# MainBoard.net
KiCad netlist of a schematic drawn in EAGLE
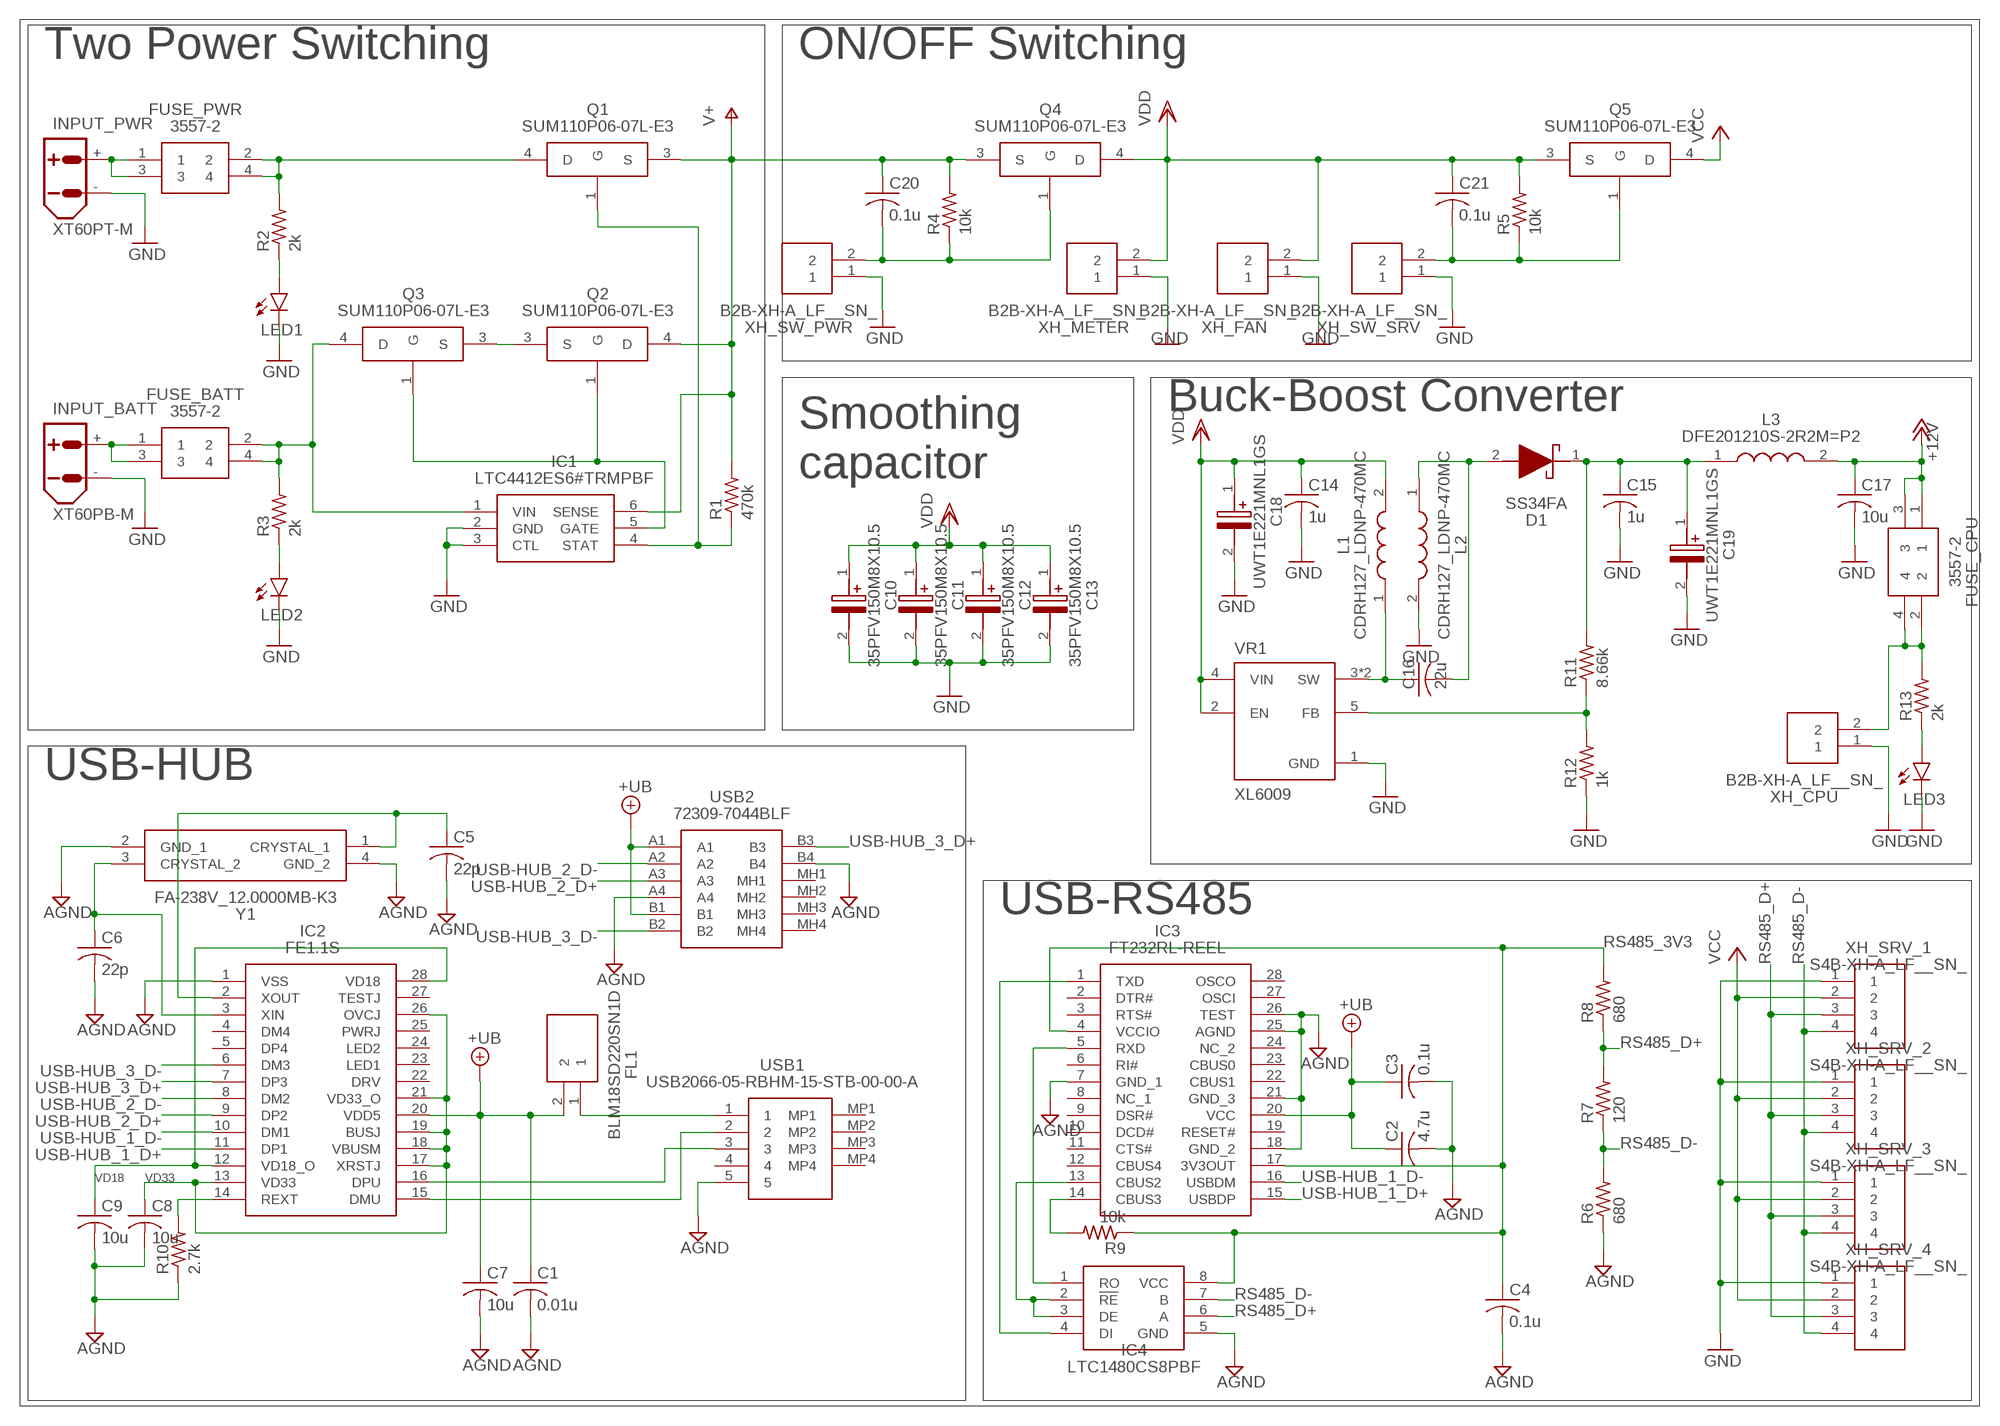
[diagram p0: schematic, sheet 1]

(export (version "E")
  (design (tool "Eeschema 10.0.6"))
  (components
    (comp (ref "C1")
      (value "0.01u")
      (footprint "eagle-import:C1608")
      (libsource (lib "eagle-import") (part "C-USC1608"))
    )
    (comp (ref "C2")
      (value "4.7u")
      (footprint "eagle-import:C1608")
      (libsource (lib "eagle-import") (part "C-USC1608"))
    )
    (comp (ref "C3")
      (value "0.1u")
      (footprint "eagle-import:C1608")
      (libsource (lib "eagle-import") (part "C-USC1608"))
    )
    (comp (ref "C4")
      (value "0.1u")
      (footprint "eagle-import:C1608")
      (libsource (lib "eagle-import") (part "C-USC1608"))
    )
    (comp (ref "C5")
      (value "22p")
      (footprint "eagle-import:C1608")
      (libsource (lib "eagle-import") (part "C-USC1608"))
    )
    (comp (ref "C6")
      (value "22p")
      (footprint "eagle-import:C1608")
      (libsource (lib "eagle-import") (part "C-USC1608"))
    )
    (comp (ref "C7")
      (value "10u")
      (footprint "eagle-import:C1608")
      (libsource (lib "eagle-import") (part "C-USC1608"))
    )
    (comp (ref "C8")
      (value "10u")
      (footprint "eagle-import:C1608")
      (libsource (lib "eagle-import") (part "C-USC1608"))
    )
    (comp (ref "C9")
      (value "10u")
      (footprint "eagle-import:C1608")
      (libsource (lib "eagle-import") (part "C-USC1608"))
    )
    (comp (ref "C10")
      (value "35PFV150M8X10.5")
      (footprint "eagle-import:CAPAE830X1050N")
      (fields (field (name "MOUSER_PART_NUMBER") "232-35PFV150M8X10.5"))
      (libsource (lib "eagle-import") (part "35PFV150M8X10.5"))
    )
    (comp (ref "C11")
      (value "35PFV150M8X10.5")
      (footprint "eagle-import:CAPAE830X1050N")
      (fields (field (name "MOUSER_PART_NUMBER") "232-35PFV150M8X10.5"))
      (libsource (lib "eagle-import") (part "35PFV150M8X10.5"))
    )
    (comp (ref "C12")
      (value "35PFV150M8X10.5")
      (footprint "eagle-import:CAPAE830X1050N")
      (fields (field (name "MOUSER_PART_NUMBER") "232-35PFV150M8X10.5"))
      (libsource (lib "eagle-import") (part "35PFV150M8X10.5"))
    )
    (comp (ref "C13")
      (value "35PFV150M8X10.5")
      (footprint "eagle-import:CAPAE830X1050N")
      (fields (field (name "MOUSER_PART_NUMBER") "232-35PFV150M8X10.5"))
      (libsource (lib "eagle-import") (part "35PFV150M8X10.5"))
    )
    (comp (ref "C14")
      (value "1u")
      (footprint "eagle-import:C1608")
      (libsource (lib "eagle-import") (part "C-USC1608"))
    )
    (comp (ref "C15")
      (value "1u")
      (footprint "eagle-import:C1608")
      (libsource (lib "eagle-import") (part "C-USC1608"))
    )
    (comp (ref "C16")
      (value "22u")
      (footprint "eagle-import:C2012")
      (libsource (lib "eagle-import") (part "C-USC2012"))
    )
    (comp (ref "C17")
      (value "10u")
      (footprint "eagle-import:C1608")
      (libsource (lib "eagle-import") (part "C-USC1608"))
    )
    (comp (ref "C18")
      (value "UWT1E221MNL1GS")
      (footprint "eagle-import:CAPAE830X1080N")
      (fields (field (name "MOUSER_PART_NUMBER") "647-UWT1E221MNL1GS"))
      (libsource (lib "eagle-import") (part "UWT1E221MNL1GS"))
    )
    (comp (ref "C19")
      (value "UWT1E221MNL1GS")
      (footprint "eagle-import:CAPAE830X1080N")
      (fields (field (name "MOUSER_PART_NUMBER") "647-UWT1E221MNL1GS"))
      (libsource (lib "eagle-import") (part "UWT1E221MNL1GS"))
    )
    (comp (ref "C20")
      (value "0.1u")
      (footprint "eagle-import:C1608")
      (libsource (lib "eagle-import") (part "C-USC1608"))
    )
    (comp (ref "C21")
      (value "0.1u")
      (footprint "eagle-import:C1608")
      (libsource (lib "eagle-import") (part "C-USC1608"))
    )
    (comp (ref "D1")
      (value "SS34FA")
      (footprint "eagle-import:SODFL3618X143N")
      (fields (field (name "MOUSER_PART_NUMBER") "512-SS34FA"))
      (libsource (lib "eagle-import") (part "SS34FA"))
    )
    (comp (ref "FL1")
      (value "BLM18SD220SN1D")
      (footprint "eagle-import:BLM18AG102BH1D")
      (fields (field (name "MOUSER_PART_NUMBER") "81-BLM18SD220SN1D"))
      (libsource (lib "eagle-import") (part "BLM18SD220SN1D"))
    )
    (comp (ref "FUSE_BATT")
      (value "3557-2")
      (footprint "eagle-import:3557-2")
      (fields (field (name "MOUSER_PART_NUMBER") "534-3557-2"))
      (libsource (lib "eagle-import") (part "3557-2"))
    )
    (comp (ref "FUSE_CPU")
      (value "3557-2")
      (footprint "eagle-import:3557-2")
      (fields (field (name "MOUSER_PART_NUMBER") "534-3557-2"))
      (libsource (lib "eagle-import") (part "3557-2"))
    )
    (comp (ref "FUSE_PWR")
      (value "3557-2")
      (footprint "eagle-import:3557-2")
      (fields (field (name "MOUSER_PART_NUMBER") "534-3557-2"))
      (libsource (lib "eagle-import") (part "3557-2"))
    )
    (comp (ref "IC1")
      (value "LTC4412ES6#TRMPBF")
      (footprint "eagle-import:SOT95P280X100-6N")
      (fields (field (name "MOUSER_PART_NUMBER") "584-LTC4412ES6TRMPBF"))
      (libsource (lib "eagle-import") (part "LTC4412ES6#TRMPBF"))
    )
    (comp (ref "IC2")
      (value "FE1.1S")
      (footprint "eagle-import:SOP64P600X175-28N")
      (libsource (lib "eagle-import") (part "FE1.1S"))
    )
    (comp (ref "IC3")
      (value "FT232RL-REEL")
      (footprint "eagle-import:SOP65P778X200-28N")
      (fields (field (name "MOUSER_PART_NUMBER") "895-FT232RL"))
      (libsource (lib "eagle-import") (part "FT232RL-REEL"))
    )
    (comp (ref "IC4")
      (value "LTC1480CS8PBF")
      (footprint "eagle-import:SOIC127P599X175-8N")
      (libsource (lib "eagle-import") (part "LTC1480CS8PBF"))
    )
    (comp (ref "INPUT_BATT")
      (value "XT60PB-M")
      (footprint "eagle-import:XT60PB-M")
      (libsource (lib "eagle-import") (part "XT60PB-M"))
    )
    (comp (ref "INPUT_PWR")
      (value "XT60PT-M")
      (footprint "eagle-import:XT60PT-M")
      (libsource (lib "eagle-import") (part "XT60PT-M"))
    )
    (comp (ref "L1")
      (value "CDRH127_LDNP-470MC")
      (footprint "eagle-import:INDPM120120X800N")
      (fields
        (field (name "MANUFACTURER_PART_NUMBER") "CDRH127/LDNP-470MC")
        (field (name "MOUSER_PART_NUMBER") "851-CDRH127LDNP470MC")
      )
      (libsource (lib "eagle-import") (part "CDRH127_LDNP-470MC"))
    )
    (comp (ref "L2")
      (value "CDRH127_LDNP-470MC")
      (footprint "eagle-import:INDPM120120X800N")
      (fields
        (field (name "MANUFACTURER_PART_NUMBER") "CDRH127/LDNP-470MC")
        (field (name "MOUSER_PART_NUMBER") "851-CDRH127LDNP470MC")
      )
      (libsource (lib "eagle-import") (part "CDRH127_LDNP-470MC"))
    )
    (comp (ref "L3")
      (value "DFE201210S-2R2M=P2")
      (footprint "eagle-import:DFE201210S1R0MP2")
      (fields (field (name "MOUSER_PART_NUMBER") "81-DFE201210S-2R2MP2"))
      (libsource (lib "eagle-import") (part "DFE201210S-2R2M=P2"))
    )
    (comp (ref "LED1")
      (value "LEDSML0603")
      (footprint "eagle-import:SML0603")
      (libsource (lib "eagle-import") (part "LEDSML0603"))
    )
    (comp (ref "LED2")
      (value "LEDSML0603")
      (footprint "eagle-import:SML0603")
      (libsource (lib "eagle-import") (part "LEDSML0603"))
    )
    (comp (ref "LED3")
      (value "LEDSML0603")
      (footprint "eagle-import:SML0603")
      (libsource (lib "eagle-import") (part "LEDSML0603"))
    )
    (comp (ref "Q1")
      (value "SUM110P06-07L-E3")
      (footprint "eagle-import:TO254P1524X483-4N")
      (fields (field (name "MOUSER_PART_NUMBER") "781-SUM110P06-07L-E3"))
      (libsource (lib "eagle-import") (part "SUM110P06-07L-E3"))
    )
    (comp (ref "Q2")
      (value "SUM110P06-07L-E3")
      (footprint "eagle-import:TO254P1524X483-4N")
      (fields (field (name "MOUSER_PART_NUMBER") "781-SUM110P06-07L-E3"))
      (libsource (lib "eagle-import") (part "SUM110P06-07L-E3"))
    )
    (comp (ref "Q3")
      (value "SUM110P06-07L-E3")
      (footprint "eagle-import:TO254P1524X483-4N")
      (fields (field (name "MOUSER_PART_NUMBER") "781-SUM110P06-07L-E3"))
      (libsource (lib "eagle-import") (part "SUM110P06-07L-E3"))
    )
    (comp (ref "Q4")
      (value "SUM110P06-07L-E3")
      (footprint "eagle-import:TO254P1524X483-4N")
      (fields (field (name "MOUSER_PART_NUMBER") "781-SUM110P06-07L-E3"))
      (libsource (lib "eagle-import") (part "SUM110P06-07L-E3"))
    )
    (comp (ref "Q5")
      (value "SUM110P06-07L-E3")
      (footprint "eagle-import:TO254P1524X483-4N")
      (fields (field (name "MOUSER_PART_NUMBER") "781-SUM110P06-07L-E3"))
      (libsource (lib "eagle-import") (part "SUM110P06-07L-E3"))
    )
    (comp (ref "R1")
      (value "470k")
      (footprint "eagle-import:R0603")
      (libsource (lib "eagle-import") (part "R-US_R0603"))
    )
    (comp (ref "R2")
      (value "2k")
      (footprint "eagle-import:R0603")
      (libsource (lib "eagle-import") (part "R-US_R0603"))
    )
    (comp (ref "R3")
      (value "2k")
      (footprint "eagle-import:R0603")
      (libsource (lib "eagle-import") (part "R-US_R0603"))
    )
    (comp (ref "R4")
      (value "10k")
      (footprint "eagle-import:R0603")
      (libsource (lib "eagle-import") (part "R-US_R0603"))
    )
    (comp (ref "R5")
      (value "10k")
      (footprint "eagle-import:R0603")
      (libsource (lib "eagle-import") (part "R-US_R0603"))
    )
    (comp (ref "R6")
      (value "680")
      (footprint "eagle-import:R0603")
      (libsource (lib "eagle-import") (part "R-US_R0603"))
    )
    (comp (ref "R7")
      (value "120")
      (footprint "eagle-import:R0603")
      (libsource (lib "eagle-import") (part "R-US_R0603"))
    )
    (comp (ref "R8")
      (value "680")
      (footprint "eagle-import:R0603")
      (libsource (lib "eagle-import") (part "R-US_R0603"))
    )
    (comp (ref "R9")
      (value "10k")
      (footprint "eagle-import:R0603")
      (libsource (lib "eagle-import") (part "R-US_R0603"))
    )
    (comp (ref "R10")
      (value "2.7k")
      (footprint "eagle-import:R0603")
      (libsource (lib "eagle-import") (part "R-US_R0603"))
    )
    (comp (ref "R11")
      (value "8.66k")
      (footprint "eagle-import:R0603")
      (libsource (lib "eagle-import") (part "R-US_R0603"))
    )
    (comp (ref "R12")
      (value "1k")
      (footprint "eagle-import:R0603")
      (libsource (lib "eagle-import") (part "R-US_R0603"))
    )
    (comp (ref "R13")
      (value "2k")
      (footprint "eagle-import:R0603")
      (libsource (lib "eagle-import") (part "R-US_R0603"))
    )
    (comp (ref "USB1")
      (value "USB2066-05-RBHM-15-STB-00-00-A")
      (footprint "eagle-import:USB206605RBHM15STB0000A")
      (fields (field (name "MOUSER_PART_NUMBER") "640-2665RBHM15STB00A"))
      (libsource (lib "eagle-import") (part "USB2066-05-RBHM-15-STB-00-00-A"))
    )
    (comp (ref "USB2")
      (value "72309-7044BLF")
      (footprint "eagle-import:723097044BLF")
      (libsource (lib "eagle-import") (part "72309-7044BLF"))
    )
    (comp (ref "VR1")
      (value "XL6009")
      (footprint "eagle-import:DPAK170P1435X465-6N")
      (fields (field (name "MF") "XLSEMI"))
      (libsource (lib "eagle-import") (part "XL6009"))
    )
    (comp (ref "XH_CPU")
      (value "B2B-XH-A_LF__SN_")
      (footprint "eagle-import:SHDR2W64P0X250_1X2_740X575X700")
      (fields (field (name "MANUFACTURER_PART_NUMBER") "B2B-XH-A(LF)(SN)"))
      (libsource (lib "eagle-import") (part "B2B-XH-A_LF__SN_"))
    )
    (comp (ref "XH_FAN")
      (value "B2B-XH-A_LF__SN_")
      (footprint "eagle-import:SHDR2W64P0X250_1X2_740X575X700")
      (fields (field (name "MANUFACTURER_PART_NUMBER") "B2B-XH-A(LF)(SN)"))
      (libsource (lib "eagle-import") (part "B2B-XH-A_LF__SN_"))
    )
    (comp (ref "XH_METER")
      (value "B2B-XH-A_LF__SN_")
      (footprint "eagle-import:SHDR2W64P0X250_1X2_740X575X700")
      (fields (field (name "MANUFACTURER_PART_NUMBER") "B2B-XH-A(LF)(SN)"))
      (libsource (lib "eagle-import") (part "B2B-XH-A_LF__SN_"))
    )
    (comp (ref "XH_SRV_1")
      (value "S4B-XH-A_LF__SN_")
      (footprint "eagle-import:SHDRRA4W64P0X250_1X4_1240X1150")
      (fields (field (name "MANUFACTURER_PART_NUMBER") "S4B-XH-A(LF)(SN)"))
      (libsource (lib "eagle-import") (part "S4B-XH-A_LF__SN_"))
    )
    (comp (ref "XH_SRV_2")
      (value "S4B-XH-A_LF__SN_")
      (footprint "eagle-import:SHDRRA4W64P0X250_1X4_1240X1150")
      (fields (field (name "MANUFACTURER_PART_NUMBER") "S4B-XH-A(LF)(SN)"))
      (libsource (lib "eagle-import") (part "S4B-XH-A_LF__SN_"))
    )
    (comp (ref "XH_SRV_3")
      (value "S4B-XH-A_LF__SN_")
      (footprint "eagle-import:SHDRRA4W64P0X250_1X4_1240X1150")
      (fields (field (name "MANUFACTURER_PART_NUMBER") "S4B-XH-A(LF)(SN)"))
      (libsource (lib "eagle-import") (part "S4B-XH-A_LF__SN_"))
    )
    (comp (ref "XH_SRV_4")
      (value "S4B-XH-A_LF__SN_")
      (footprint "eagle-import:SHDRRA4W64P0X250_1X4_1240X1150")
      (fields (field (name "MANUFACTURER_PART_NUMBER") "S4B-XH-A(LF)(SN)"))
      (libsource (lib "eagle-import") (part "S4B-XH-A_LF__SN_"))
    )
    (comp (ref "XH_SW_PWR")
      (value "B2B-XH-A_LF__SN_")
      (footprint "eagle-import:SHDR2W64P0X250_1X2_740X575X700")
      (fields (field (name "MANUFACTURER_PART_NUMBER") "B2B-XH-A(LF)(SN)"))
      (libsource (lib "eagle-import") (part "B2B-XH-A_LF__SN_"))
    )
    (comp (ref "XH_SW_SRV")
      (value "B2B-XH-A_LF__SN_")
      (footprint "eagle-import:SHDR2W64P0X250_1X2_740X575X700")
      (fields (field (name "MANUFACTURER_PART_NUMBER") "B2B-XH-A(LF)(SN)"))
      (libsource (lib "eagle-import") (part "B2B-XH-A_LF__SN_"))
    )
    (comp (ref "Y1")
      (value "FA-238V_12.0000MB-K3")
      (footprint "eagle-import:FA238V120000MBK3")
      (fields
        (field (name "MANUFACTURER_PART_NUMBER") "FA-238V 12.0000MB-K3")
        (field (name "MOUSER_PART_NUMBER") "732-FA238V12.B-K3")
      )
      (libsource (lib "eagle-import") (part "FA-238V_12.0000MB-K3"))
    )
  )
  (nets
    (net (code "1") (name "+12V") (class "Default")
      (node (ref "C17") (pin "1") (pinfunction "1_1") (pintype "passive"))
      (node (ref "FUSE_CPU") (pin "1") (pinfunction "1_1") (pintype "bidirectional"))
      (node (ref "FUSE_CPU") (pin "3") (pinfunction "3_3") (pintype "bidirectional"))
      (node (ref "L3") (pin "2") (pinfunction "2_2") (pintype "bidirectional"))
    )
    (net (code "2") (name "+UB") (class "Default")
      (node (ref "C1") (pin "1") (pinfunction "1_1") (pintype "passive"))
      (node (ref "C2") (pin "1") (pinfunction "1_1") (pintype "passive"))
      (node (ref "C3") (pin "1") (pinfunction "1_1") (pintype "passive"))
      (node (ref "C7") (pin "1") (pinfunction "1_1") (pintype "passive"))
      (node (ref "FL1") (pin "2") (pinfunction "2_2") (pintype "bidirectional"))
      (node (ref "IC2") (pin "20") (pinfunction "VDD5_20") (pintype "bidirectional"))
      (node (ref "IC3") (pin "20") (pinfunction "VCC_20") (pintype "bidirectional"))
      (node (ref "USB2") (pin "A1") (pinfunction "A1_A1") (pintype "bidirectional"))
      (node (ref "USB2") (pin "B1") (pinfunction "B1_B1") (pintype "bidirectional"))
    )
    (net (code "3") (name "/RS485_3V3") (class "Default")
      (node (ref "C4") (pin "1") (pinfunction "1_1") (pintype "passive"))
      (node (ref "IC3") (pin "17") (pinfunction "3V3OUT_17") (pintype "bidirectional"))
      (node (ref "IC3") (pin "4") (pinfunction "VCCIO_4") (pintype "bidirectional"))
      (node (ref "IC4") (pin "8") (pinfunction "VCC_8") (pintype "bidirectional"))
      (node (ref "R8") (pin "2") (pinfunction "2_2") (pintype "passive"))
      (node (ref "R9") (pin "1") (pinfunction "1_1") (pintype "passive"))
    )
    (net (code "4") (name "/RS485_D+") (class "Default")
      (node (ref "IC4") (pin "6") (pinfunction "A_6") (pintype "bidirectional"))
      (node (ref "R7") (pin "2") (pinfunction "2_2") (pintype "passive"))
      (node (ref "R8") (pin "1") (pinfunction "1_1") (pintype "passive"))
      (node (ref "XH_SRV_1") (pin "3") (pinfunction "3_3") (pintype "bidirectional"))
      (node (ref "XH_SRV_2") (pin "3") (pinfunction "3_3") (pintype "bidirectional"))
      (node (ref "XH_SRV_3") (pin "3") (pinfunction "3_3") (pintype "bidirectional"))
      (node (ref "XH_SRV_4") (pin "3") (pinfunction "3_3") (pintype "bidirectional"))
    )
    (net (code "5") (name "/RS485_D-") (class "Default")
      (node (ref "IC4") (pin "7") (pinfunction "B_7") (pintype "bidirectional"))
      (node (ref "R6") (pin "2") (pinfunction "2_2") (pintype "passive"))
      (node (ref "R7") (pin "1") (pinfunction "1_1") (pintype "passive"))
      (node (ref "XH_SRV_1") (pin "4") (pinfunction "4_4") (pintype "bidirectional"))
      (node (ref "XH_SRV_2") (pin "4") (pinfunction "4_4") (pintype "bidirectional"))
      (node (ref "XH_SRV_3") (pin "4") (pinfunction "4_4") (pintype "bidirectional"))
      (node (ref "XH_SRV_4") (pin "4") (pinfunction "4_4") (pintype "bidirectional"))
    )
    (net (code "6") (name "/USB-HUB_1_D+") (class "Default")
      (node (ref "IC2") (pin "11") (pinfunction "DP1_11") (pintype "bidirectional"))
      (node (ref "IC3") (pin "15") (pinfunction "USBDP_15") (pintype "bidirectional"))
    )
    (net (code "7") (name "/USB-HUB_1_D-") (class "Default")
      (node (ref "IC2") (pin "10") (pinfunction "DM1_10") (pintype "bidirectional"))
      (node (ref "IC3") (pin "16") (pinfunction "USBDM_16") (pintype "bidirectional"))
    )
    (net (code "8") (name "/USB-HUB_2_D+") (class "Default")
      (node (ref "IC2") (pin "9") (pinfunction "DP2_9") (pintype "bidirectional"))
      (node (ref "USB2") (pin "A3") (pinfunction "A3_A3") (pintype "bidirectional"))
    )
    (net (code "9") (name "/USB-HUB_2_D-") (class "Default")
      (node (ref "IC2") (pin "8") (pinfunction "DM2_8") (pintype "bidirectional"))
      (node (ref "USB2") (pin "A2") (pinfunction "A2_A2") (pintype "bidirectional"))
    )
    (net (code "10") (name "/USB-HUB_3_D+") (class "Default")
      (node (ref "IC2") (pin "7") (pinfunction "DP3_7") (pintype "bidirectional"))
      (node (ref "USB2") (pin "B3") (pinfunction "B3_B3") (pintype "bidirectional"))
    )
    (net (code "11") (name "/USB-HUB_3_D-") (class "Default")
      (node (ref "IC2") (pin "6") (pinfunction "DM3_6") (pintype "bidirectional"))
      (node (ref "USB2") (pin "B2") (pinfunction "B2_B2") (pintype "bidirectional"))
    )
    (net (code "12") (name "/VD18") (class "Default")
      (node (ref "C9") (pin "1") (pinfunction "1_1") (pintype "passive"))
      (node (ref "IC2") (pin "12") (pinfunction "VD18_O_12") (pintype "bidirectional"))
      (node (ref "IC2") (pin "28") (pinfunction "VD18_28") (pintype "bidirectional"))
    )
    (net (code "13") (name "/VD33") (class "Default")
      (node (ref "C8") (pin "1") (pinfunction "1_1") (pintype "passive"))
      (node (ref "IC2") (pin "13") (pinfunction "VD33_13") (pintype "bidirectional"))
      (node (ref "IC2") (pin "17") (pinfunction "XRSTJ_17") (pintype "bidirectional"))
      (node (ref "IC2") (pin "18") (pinfunction "VBUSM_18") (pintype "bidirectional"))
      (node (ref "IC2") (pin "19") (pinfunction "BUSJ_19") (pintype "bidirectional"))
      (node (ref "IC2") (pin "21") (pinfunction "VD33_O_21") (pintype "bidirectional"))
      (node (ref "IC2") (pin "26") (pinfunction "OVCJ_26") (pintype "bidirectional"))
    )
    (net (code "14") (name "AGND") (class "Default")
      (node (ref "C1") (pin "2") (pinfunction "2_2") (pintype "passive"))
      (node (ref "C2") (pin "2") (pinfunction "2_2") (pintype "passive"))
      (node (ref "C3") (pin "2") (pinfunction "2_2") (pintype "passive"))
      (node (ref "C4") (pin "2") (pinfunction "2_2") (pintype "passive"))
      (node (ref "C5") (pin "2") (pinfunction "2_2") (pintype "passive"))
      (node (ref "C6") (pin "2") (pinfunction "2_2") (pintype "passive"))
      (node (ref "C7") (pin "2") (pinfunction "2_2") (pintype "passive"))
      (node (ref "C8") (pin "2") (pinfunction "2_2") (pintype "passive"))
      (node (ref "C9") (pin "2") (pinfunction "2_2") (pintype "passive"))
      (node (ref "IC2") (pin "1") (pinfunction "VSS_1") (pintype "bidirectional"))
      (node (ref "IC3") (pin "18") (pinfunction "GND_2_18") (pintype "bidirectional"))
      (node (ref "IC3") (pin "21") (pinfunction "GND_3_21") (pintype "bidirectional"))
      (node (ref "IC3") (pin "25") (pinfunction "AGND_25") (pintype "bidirectional"))
      (node (ref "IC3") (pin "26") (pinfunction "TEST_26") (pintype "bidirectional"))
      (node (ref "IC3") (pin "7") (pinfunction "GND_1_7") (pintype "bidirectional"))
      (node (ref "IC4") (pin "5") (pinfunction "GND_5") (pintype "bidirectional"))
      (node (ref "R10") (pin "1") (pinfunction "1_1") (pintype "passive"))
      (node (ref "R6") (pin "1") (pinfunction "1_1") (pintype "passive"))
      (node (ref "USB1") (pin "5") (pinfunction "5_5") (pintype "bidirectional"))
      (node (ref "USB2") (pin "A4") (pinfunction "A4_A4") (pintype "bidirectional"))
      (node (ref "USB2") (pin "B4") (pinfunction "B4_B4") (pintype "bidirectional"))
      (node (ref "Y1") (pin "2") (pinfunction "GND_1_2") (pintype "bidirectional"))
      (node (ref "Y1") (pin "4") (pinfunction "GND_2_4") (pintype "bidirectional"))
    )
    (net (code "15") (name "GND") (class "Default")
      (node (ref "C10") (pin "2") (pinfunction "-_2") (pintype "bidirectional"))
      (node (ref "C11") (pin "2") (pinfunction "-_2") (pintype "bidirectional"))
      (node (ref "C12") (pin "2") (pinfunction "-_2") (pintype "bidirectional"))
      (node (ref "C13") (pin "2") (pinfunction "-_2") (pintype "bidirectional"))
      (node (ref "C14") (pin "2") (pinfunction "2_2") (pintype "passive"))
      (node (ref "C15") (pin "2") (pinfunction "2_2") (pintype "passive"))
      (node (ref "C17") (pin "2") (pinfunction "2_2") (pintype "passive"))
      (node (ref "C18") (pin "2") (pinfunction "-_2") (pintype "bidirectional"))
      (node (ref "C19") (pin "2") (pinfunction "-_2") (pintype "bidirectional"))
      (node (ref "IC1") (pin "2") (pinfunction "GND_2") (pintype "power_in"))
      (node (ref "IC1") (pin "3") (pinfunction "CTL_3") (pintype "input"))
      (node (ref "INPUT_BATT") (pin "-") (pinfunction "-_-") (pintype "power_in"))
      (node (ref "INPUT_PWR") (pin "-") (pinfunction "-_-") (pintype "power_in"))
      (node (ref "L2") (pin "2") (pinfunction "2_2") (pintype "bidirectional"))
      (node (ref "LED1") (pin "C") (pinfunction "C_C") (pintype "passive"))
      (node (ref "LED2") (pin "C") (pinfunction "C_C") (pintype "passive"))
      (node (ref "LED3") (pin "C") (pinfunction "C_C") (pintype "passive"))
      (node (ref "R12") (pin "1") (pinfunction "1_1") (pintype "passive"))
      (node (ref "VR1") (pin "1") (pinfunction "GND_1") (pintype "power_in"))
      (node (ref "XH_CPU") (pin "1") (pinfunction "1_1") (pintype "bidirectional"))
      (node (ref "XH_FAN") (pin "1") (pinfunction "1_1") (pintype "bidirectional"))
      (node (ref "XH_METER") (pin "1") (pinfunction "1_1") (pintype "bidirectional"))
      (node (ref "XH_SRV_1") (pin "1") (pinfunction "1_1") (pintype "bidirectional"))
      (node (ref "XH_SRV_2") (pin "1") (pinfunction "1_1") (pintype "bidirectional"))
      (node (ref "XH_SRV_3") (pin "1") (pinfunction "1_1") (pintype "bidirectional"))
      (node (ref "XH_SRV_4") (pin "1") (pinfunction "1_1") (pintype "bidirectional"))
      (node (ref "XH_SW_PWR") (pin "1") (pinfunction "1_1") (pintype "bidirectional"))
      (node (ref "XH_SW_SRV") (pin "1") (pinfunction "1_1") (pintype "bidirectional"))
    )
    (net (code "16") (name "Net-(C16-Pad1)") (class "Default")
      (node (ref "C16") (pin "1") (pinfunction "1_1") (pintype "passive"))
      (node (ref "L1") (pin "1") (pinfunction "1_1") (pintype "bidirectional"))
      (node (ref "VR1") (pin "3") (pinfunction "SW_3") (pintype "output"))
      (node (ref "VR1") (pin "6") (pinfunction "SW_6") (pintype "output"))
    )
    (net (code "17") (name "Net-(C19-+)") (class "Default")
      (node (ref "C15") (pin "1") (pinfunction "1_1") (pintype "passive"))
      (node (ref "C19") (pin "1") (pinfunction "+_1") (pintype "bidirectional"))
      (node (ref "D1") (pin "1") (pinfunction "K_1") (pintype "bidirectional"))
      (node (ref "L3") (pin "1") (pinfunction "1_1") (pintype "bidirectional"))
      (node (ref "R11") (pin "2") (pinfunction "2_2") (pintype "passive"))
    )
    (net (code "18") (name "Net-(D1-A)") (class "Default")
      (node (ref "C16") (pin "2") (pinfunction "2_2") (pintype "passive"))
      (node (ref "D1") (pin "2") (pinfunction "A_2") (pintype "bidirectional"))
      (node (ref "L2") (pin "1") (pinfunction "1_1") (pintype "bidirectional"))
    )
    (net (code "19") (name "Net-(FL1-Pad1)") (class "Default")
      (node (ref "FL1") (pin "1") (pinfunction "1_1") (pintype "bidirectional"))
      (node (ref "USB1") (pin "1") (pinfunction "1_1") (pintype "bidirectional"))
    )
    (net (code "20") (name "Net-(FUSE_BATT-Pad1)") (class "Default")
      (node (ref "FUSE_BATT") (pin "1") (pinfunction "1_1") (pintype "bidirectional"))
      (node (ref "FUSE_BATT") (pin "3") (pinfunction "3_3") (pintype "bidirectional"))
      (node (ref "INPUT_BATT") (pin "+") (pinfunction "+_+") (pintype "power_in"))
    )
    (net (code "21") (name "Net-(FUSE_CPU-Pad2)") (class "Default")
      (node (ref "FUSE_CPU") (pin "2") (pinfunction "2_2") (pintype "bidirectional"))
      (node (ref "FUSE_CPU") (pin "4") (pinfunction "4_4") (pintype "bidirectional"))
      (node (ref "R13") (pin "2") (pinfunction "2_2") (pintype "passive"))
      (node (ref "XH_CPU") (pin "2") (pinfunction "2_2") (pintype "bidirectional"))
    )
    (net (code "22") (name "Net-(FUSE_PWR-Pad1)") (class "Default")
      (node (ref "FUSE_PWR") (pin "1") (pinfunction "1_1") (pintype "bidirectional"))
      (node (ref "FUSE_PWR") (pin "3") (pinfunction "3_3") (pintype "bidirectional"))
      (node (ref "INPUT_PWR") (pin "+") (pinfunction "+_+") (pintype "power_in"))
    )
    (net (code "23") (name "Net-(IC1-GATE)") (class "Default")
      (node (ref "IC1") (pin "5") (pinfunction "GATE_5") (pintype "output"))
      (node (ref "Q2") (pin "1") (pinfunction "G_1") (pintype "bidirectional"))
      (node (ref "Q3") (pin "1") (pinfunction "G_1") (pintype "bidirectional"))
    )
    (net (code "24") (name "Net-(IC1-STAT)") (class "Default")
      (node (ref "IC1") (pin "4") (pinfunction "STAT_4") (pintype "output"))
      (node (ref "Q1") (pin "1") (pinfunction "G_1") (pintype "bidirectional"))
      (node (ref "R1") (pin "1") (pinfunction "1_1") (pintype "passive"))
    )
    (net (code "25") (name "Net-(IC1-VIN)") (class "Default")
      (node (ref "FUSE_BATT") (pin "2") (pinfunction "2_2") (pintype "bidirectional"))
      (node (ref "FUSE_BATT") (pin "4") (pinfunction "4_4") (pintype "bidirectional"))
      (node (ref "IC1") (pin "1") (pinfunction "VIN_1") (pintype "power_in"))
      (node (ref "Q3") (pin "4") (pinfunction "D_4") (pintype "bidirectional"))
      (node (ref "R3") (pin "2") (pinfunction "2_2") (pintype "passive"))
    )
    (net (code "26") (name "Net-(IC2-DMU)") (class "Default")
      (node (ref "IC2") (pin "15") (pinfunction "DMU_15") (pintype "bidirectional"))
      (node (ref "USB1") (pin "2") (pinfunction "2_2") (pintype "bidirectional"))
    )
    (net (code "27") (name "Net-(IC2-DPU)") (class "Default")
      (node (ref "IC2") (pin "16") (pinfunction "DPU_16") (pintype "bidirectional"))
      (node (ref "USB1") (pin "3") (pinfunction "3_3") (pintype "bidirectional"))
    )
    (net (code "28") (name "Net-(IC2-REXT)") (class "Default")
      (node (ref "IC2") (pin "14") (pinfunction "REXT_14") (pintype "bidirectional"))
      (node (ref "R10") (pin "2") (pinfunction "2_2") (pintype "passive"))
    )
    (net (code "29") (name "Net-(IC2-XIN)") (class "Default")
      (node (ref "C6") (pin "1") (pinfunction "1_1") (pintype "passive"))
      (node (ref "IC2") (pin "3") (pinfunction "XIN_3") (pintype "bidirectional"))
      (node (ref "Y1") (pin "3") (pinfunction "CRYSTAL_2_3") (pintype "bidirectional"))
    )
    (net (code "30") (name "Net-(IC2-XOUT)") (class "Default")
      (node (ref "C5") (pin "1") (pinfunction "1_1") (pintype "passive"))
      (node (ref "IC2") (pin "2") (pinfunction "XOUT_2") (pintype "bidirectional"))
      (node (ref "Y1") (pin "1") (pinfunction "CRYSTAL_1_1") (pintype "bidirectional"))
    )
    (net (code "31") (name "Net-(IC3-CBUS2)") (class "Default")
      (node (ref "IC3") (pin "13") (pinfunction "CBUS2_13") (pintype "bidirectional"))
      (node (ref "IC4") (pin "2") (pinfunction "~{RE}_2") (pintype "bidirectional"))
      (node (ref "IC4") (pin "3") (pinfunction "DE_3") (pintype "bidirectional"))
    )
    (net (code "32") (name "Net-(IC3-CBUS3)") (class "Default")
      (node (ref "IC3") (pin "14") (pinfunction "CBUS3_14") (pintype "bidirectional"))
      (node (ref "R9") (pin "2") (pinfunction "2_2") (pintype "passive"))
    )
    (net (code "33") (name "Net-(IC3-RXD)") (class "Default")
      (node (ref "IC3") (pin "5") (pinfunction "RXD_5") (pintype "bidirectional"))
      (node (ref "IC4") (pin "1") (pinfunction "RO_1") (pintype "bidirectional"))
    )
    (net (code "34") (name "Net-(IC3-TXD)") (class "Default")
      (node (ref "IC3") (pin "1") (pinfunction "TXD_1") (pintype "bidirectional"))
      (node (ref "IC4") (pin "4") (pinfunction "DI_4") (pintype "bidirectional"))
    )
    (net (code "35") (name "Net-(LED1-PadA)") (class "Default")
      (node (ref "LED1") (pin "A") (pinfunction "A_A") (pintype "passive"))
      (node (ref "R2") (pin "1") (pinfunction "1_1") (pintype "passive"))
    )
    (net (code "36") (name "Net-(LED2-PadA)") (class "Default")
      (node (ref "LED2") (pin "A") (pinfunction "A_A") (pintype "passive"))
      (node (ref "R3") (pin "1") (pinfunction "1_1") (pintype "passive"))
    )
    (net (code "37") (name "Net-(LED3-PadA)") (class "Default")
      (node (ref "LED3") (pin "A") (pinfunction "A_A") (pintype "passive"))
      (node (ref "R13") (pin "1") (pinfunction "1_1") (pintype "passive"))
    )
    (net (code "38") (name "Net-(Q1-D)") (class "Default")
      (node (ref "FUSE_PWR") (pin "2") (pinfunction "2_2") (pintype "bidirectional"))
      (node (ref "FUSE_PWR") (pin "4") (pinfunction "4_4") (pintype "bidirectional"))
      (node (ref "Q1") (pin "4") (pinfunction "D_4") (pintype "bidirectional"))
      (node (ref "R2") (pin "2") (pinfunction "2_2") (pintype "passive"))
    )
    (net (code "39") (name "Net-(Q2-S)") (class "Default")
      (node (ref "Q2") (pin "3") (pinfunction "S_3") (pintype "bidirectional"))
      (node (ref "Q3") (pin "3") (pinfunction "S_3") (pintype "bidirectional"))
    )
    (net (code "40") (name "Net-(Q4-G)") (class "Default")
      (node (ref "C20") (pin "2") (pinfunction "2_2") (pintype "passive"))
      (node (ref "Q4") (pin "1") (pinfunction "G_1") (pintype "bidirectional"))
      (node (ref "R4") (pin "1") (pinfunction "1_1") (pintype "passive"))
      (node (ref "XH_SW_PWR") (pin "2") (pinfunction "2_2") (pintype "bidirectional"))
    )
    (net (code "41") (name "Net-(Q5-G)") (class "Default")
      (node (ref "C21") (pin "2") (pinfunction "2_2") (pintype "passive"))
      (node (ref "Q5") (pin "1") (pinfunction "G_1") (pintype "bidirectional"))
      (node (ref "R5") (pin "1") (pinfunction "1_1") (pintype "passive"))
      (node (ref "XH_SW_SRV") (pin "2") (pinfunction "2_2") (pintype "bidirectional"))
    )
    (net (code "42") (name "Net-(VR1-FB)") (class "Default")
      (node (ref "R11") (pin "1") (pinfunction "1_1") (pintype "passive"))
      (node (ref "R12") (pin "2") (pinfunction "2_2") (pintype "passive"))
      (node (ref "VR1") (pin "5") (pinfunction "FB_5") (pintype "input"))
    )
    (net (code "43") (name "V+") (class "Default")
      (node (ref "C20") (pin "1") (pinfunction "1_1") (pintype "passive"))
      (node (ref "IC1") (pin "6") (pinfunction "SENSE_6") (pintype "input"))
      (node (ref "Q1") (pin "3") (pinfunction "S_3") (pintype "bidirectional"))
      (node (ref "Q2") (pin "4") (pinfunction "D_4") (pintype "bidirectional"))
      (node (ref "Q4") (pin "3") (pinfunction "S_3") (pintype "bidirectional"))
      (node (ref "R1") (pin "2") (pinfunction "2_2") (pintype "passive"))
      (node (ref "R4") (pin "2") (pinfunction "2_2") (pintype "passive"))
    )
    (net (code "44") (name "VCC") (class "Default")
      (node (ref "Q5") (pin "4") (pinfunction "D_4") (pintype "bidirectional"))
      (node (ref "XH_SRV_1") (pin "2") (pinfunction "2_2") (pintype "bidirectional"))
      (node (ref "XH_SRV_2") (pin "2") (pinfunction "2_2") (pintype "bidirectional"))
      (node (ref "XH_SRV_3") (pin "2") (pinfunction "2_2") (pintype "bidirectional"))
      (node (ref "XH_SRV_4") (pin "2") (pinfunction "2_2") (pintype "bidirectional"))
    )
    (net (code "45") (name "VDD") (class "Default")
      (node (ref "C10") (pin "1") (pinfunction "+_1") (pintype "bidirectional"))
      (node (ref "C11") (pin "1") (pinfunction "+_1") (pintype "bidirectional"))
      (node (ref "C12") (pin "1") (pinfunction "+_1") (pintype "bidirectional"))
      (node (ref "C13") (pin "1") (pinfunction "+_1") (pintype "bidirectional"))
      (node (ref "C14") (pin "1") (pinfunction "1_1") (pintype "passive"))
      (node (ref "C18") (pin "1") (pinfunction "+_1") (pintype "bidirectional"))
      (node (ref "C21") (pin "1") (pinfunction "1_1") (pintype "passive"))
      (node (ref "L1") (pin "2") (pinfunction "2_2") (pintype "bidirectional"))
      (node (ref "Q4") (pin "4") (pinfunction "D_4") (pintype "bidirectional"))
      (node (ref "Q5") (pin "3") (pinfunction "S_3") (pintype "bidirectional"))
      (node (ref "R5") (pin "2") (pinfunction "2_2") (pintype "passive"))
      (node (ref "VR1") (pin "2") (pinfunction "EN_2") (pintype "input"))
      (node (ref "VR1") (pin "4") (pinfunction "VIN_4") (pintype "input"))
      (node (ref "XH_FAN") (pin "2") (pinfunction "2_2") (pintype "bidirectional"))
      (node (ref "XH_METER") (pin "2") (pinfunction "2_2") (pintype "bidirectional"))
    )
    (net (code "46") (name "unconnected-(IC2-DM4-Pad4)") (class "Default")
      (node (ref "IC2") (pin "4") (pinfunction "DM4_4") (pintype "bidirectional"))
    )
    (net (code "47") (name "unconnected-(IC2-DP4-Pad5)") (class "Default")
      (node (ref "IC2") (pin "5") (pinfunction "DP4_5") (pintype "bidirectional"))
    )
    (net (code "48") (name "unconnected-(IC2-DRV-Pad22)") (class "Default")
      (node (ref "IC2") (pin "22") (pinfunction "DRV_22") (pintype "bidirectional"))
    )
    (net (code "49") (name "unconnected-(IC2-LED1-Pad23)") (class "Default")
      (node (ref "IC2") (pin "23") (pinfunction "LED1_23") (pintype "bidirectional"))
    )
    (net (code "50") (name "unconnected-(IC2-LED2-Pad24)") (class "Default")
      (node (ref "IC2") (pin "24") (pinfunction "LED2_24") (pintype "bidirectional"))
    )
    (net (code "51") (name "unconnected-(IC2-PWRJ-Pad25)") (class "Default")
      (node (ref "IC2") (pin "25") (pinfunction "PWRJ_25") (pintype "bidirectional"))
    )
    (net (code "52") (name "unconnected-(IC2-TESTJ-Pad27)") (class "Default")
      (node (ref "IC2") (pin "27") (pinfunction "TESTJ_27") (pintype "bidirectional"))
    )
    (net (code "53") (name "unconnected-(IC3-CBUS0-Pad23)") (class "Default")
      (node (ref "IC3") (pin "23") (pinfunction "CBUS0_23") (pintype "bidirectional"))
    )
    (net (code "54") (name "unconnected-(IC3-CBUS1-Pad22)") (class "Default")
      (node (ref "IC3") (pin "22") (pinfunction "CBUS1_22") (pintype "bidirectional"))
    )
    (net (code "55") (name "unconnected-(IC3-CBUS4-Pad12)") (class "Default")
      (node (ref "IC3") (pin "12") (pinfunction "CBUS4_12") (pintype "bidirectional"))
    )
    (net (code "56") (name "unconnected-(IC3-CTS#-Pad11)") (class "Default")
      (node (ref "IC3") (pin "11") (pinfunction "CTS#_11") (pintype "bidirectional"))
    )
    (net (code "57") (name "unconnected-(IC3-DCD#-Pad10)") (class "Default")
      (node (ref "IC3") (pin "10") (pinfunction "DCD#_10") (pintype "bidirectional"))
    )
    (net (code "58") (name "unconnected-(IC3-DSR#-Pad9)") (class "Default")
      (node (ref "IC3") (pin "9") (pinfunction "DSR#_9") (pintype "bidirectional"))
    )
    (net (code "59") (name "unconnected-(IC3-DTR#-Pad2)") (class "Default")
      (node (ref "IC3") (pin "2") (pinfunction "DTR#_2") (pintype "bidirectional"))
    )
    (net (code "60") (name "unconnected-(IC3-NC_1-Pad8)") (class "Default")
      (node (ref "IC3") (pin "8") (pinfunction "NC_1_8") (pintype "bidirectional"))
    )
    (net (code "61") (name "unconnected-(IC3-NC_2-Pad24)") (class "Default")
      (node (ref "IC3") (pin "24") (pinfunction "NC_2_24") (pintype "bidirectional"))
    )
    (net (code "62") (name "unconnected-(IC3-OSCI-Pad27)") (class "Default")
      (node (ref "IC3") (pin "27") (pinfunction "OSCI_27") (pintype "bidirectional"))
    )
    (net (code "63") (name "unconnected-(IC3-OSCO-Pad28)") (class "Default")
      (node (ref "IC3") (pin "28") (pinfunction "OSCO_28") (pintype "bidirectional"))
    )
    (net (code "64") (name "unconnected-(IC3-RESET#-Pad19)") (class "Default")
      (node (ref "IC3") (pin "19") (pinfunction "RESET#_19") (pintype "bidirectional"))
    )
    (net (code "65") (name "unconnected-(IC3-RI#-Pad6)") (class "Default")
      (node (ref "IC3") (pin "6") (pinfunction "RI#_6") (pintype "bidirectional"))
    )
    (net (code "66") (name "unconnected-(IC3-RTS#-Pad3)") (class "Default")
      (node (ref "IC3") (pin "3") (pinfunction "RTS#_3") (pintype "bidirectional"))
    )
    (net (code "67") (name "unconnected-(USB1-Pad4)") (class "Default")
      (node (ref "USB1") (pin "4") (pinfunction "4_4") (pintype "bidirectional"))
    )
    (net (code "68") (name "unconnected-(USB1-PadMP1)") (class "Default")
      (node (ref "USB1") (pin "MP1") (pinfunction "MP1_MP1") (pintype "bidirectional"))
    )
    (net (code "69") (name "unconnected-(USB1-PadMP2)") (class "Default")
      (node (ref "USB1") (pin "MP2") (pinfunction "MP2_MP2") (pintype "bidirectional"))
    )
    (net (code "70") (name "unconnected-(USB1-PadMP3)") (class "Default")
      (node (ref "USB1") (pin "MP3") (pinfunction "MP3_MP3") (pintype "bidirectional"))
    )
    (net (code "71") (name "unconnected-(USB1-PadMP4)") (class "Default")
      (node (ref "USB1") (pin "MP4") (pinfunction "MP4_MP4") (pintype "bidirectional"))
    )
    (net (code "72") (name "unconnected-(USB2-PadMH1)") (class "Default")
      (node (ref "USB2") (pin "MH1") (pinfunction "MH1_MH1") (pintype "bidirectional"))
    )
    (net (code "73") (name "unconnected-(USB2-PadMH2)") (class "Default")
      (node (ref "USB2") (pin "MH2") (pinfunction "MH2_MH2") (pintype "bidirectional"))
    )
    (net (code "74") (name "unconnected-(USB2-PadMH3)") (class "Default")
      (node (ref "USB2") (pin "MH3") (pinfunction "MH3_MH3") (pintype "bidirectional"))
    )
    (net (code "75") (name "unconnected-(USB2-PadMH4)") (class "Default")
      (node (ref "USB2") (pin "MH4") (pinfunction "MH4_MH4") (pintype "bidirectional"))
    )
  )
)
